# NuPrism_MCPMT_-_QUAD_ADC_-_Rev2.net
KiCad netlist of a schematic drawn in Altium Designer
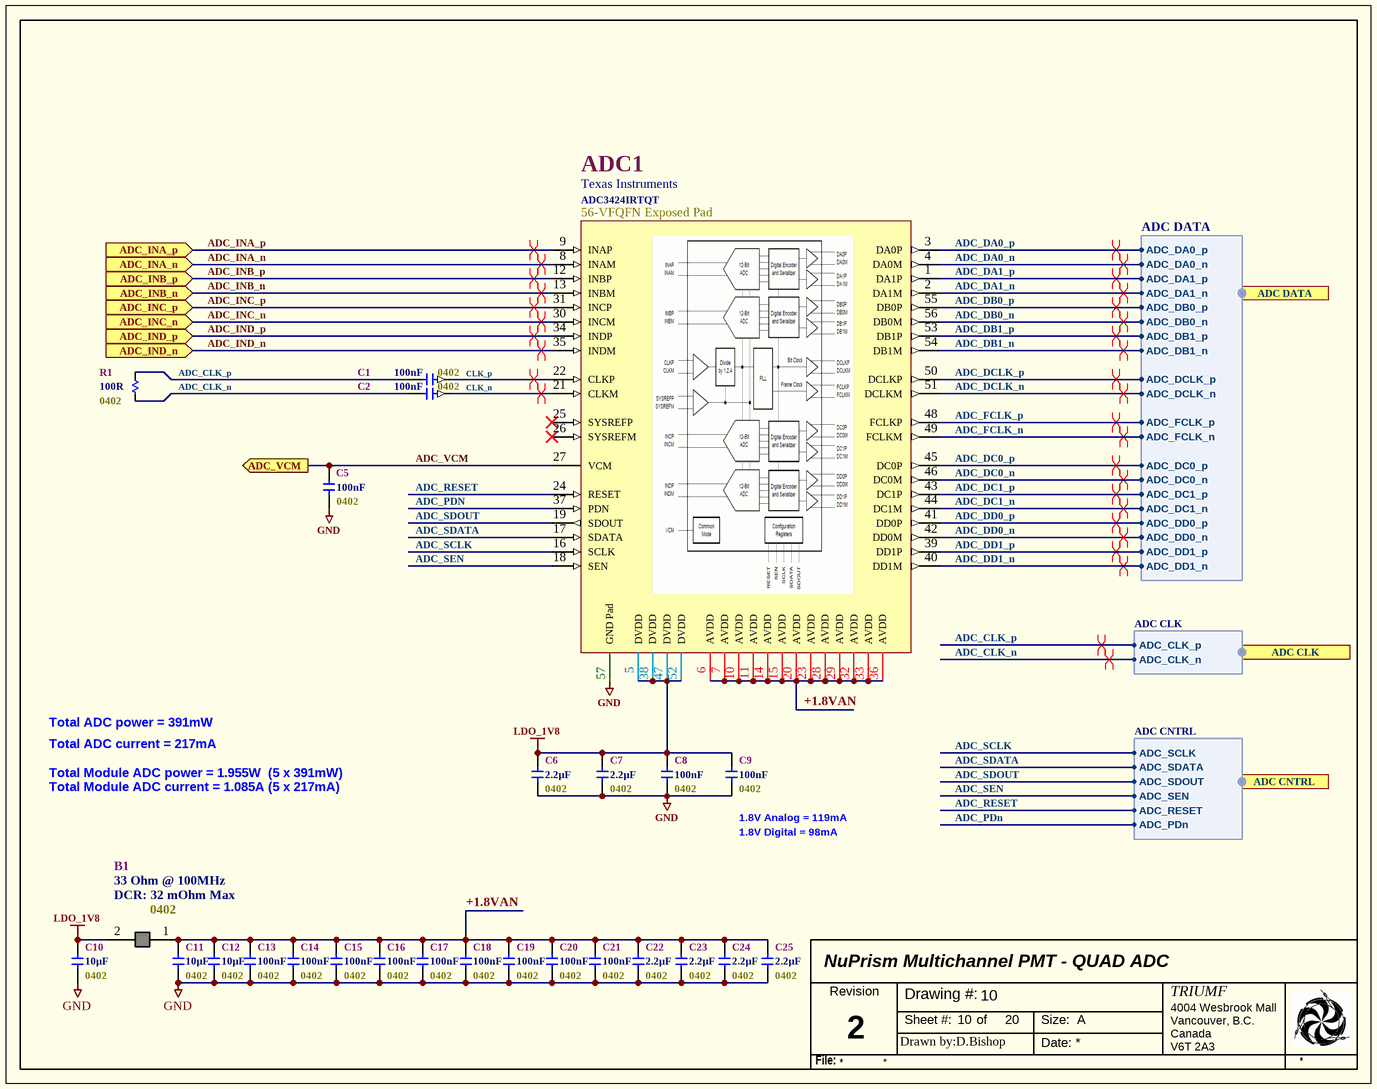
[diagram p0: NuPrism_MCPMT - QUAD ADC - Rev2.SchDoc]

(export (version "E")
  (design (tool "Eeschema 10.0.6"))
  (components
    (comp (ref "ADC1")
      (value "ADC3424IRTQT")
      (footprint "VQFN56")
      (description "12 Bit Analog to Digital Converter 4 Input 4 Pipelined 56-QFN (8x8)")
      (fields
        (field (name "MANUFACTURER") "Texas Instruments")
        (field (name "PACKAGE") "56-VFQFN Exposed Pad")
        (field (name "PARTNO") "ADC3424IRTQT")
      )
      (libsource (lib "TI_ADC") (part "ADC3424"))
    )
    (comp (ref "B1")
      (value "BLM15PX600SN1D")
      (footprint "0402")
      (description "60 Ohms @ 100MHz Ferrite Bead 0402 2.5A")
      (fields
        (field (name "MANUFACTURER") "Murata")
        (field (name "DCR") "32 mOhm Max")
        (field (name "IMPEDANCE @ FREQUENCY") "33 Ohm @ 100MHz")
        (field (name "PACKAGE") "0402")
      )
      (libsource (lib "Clock Distribution Module") (part "Ferrite Bead"))
    )
    (comp (ref "C1")
      (value "C0402C104K4RACTU")
      (footprint "0402")
      (description "SMD/SMT 0402 16V 0.1uF X7R 10%")
      (fields
        (field (name "MANUFACTURER") "Kemet")
        (field (name "CAPACITANCE") "100nF")
        (field (name "PACKAGE") "0402")
        (field (name "VOLTAGE") "16V")
      )
      (libsource (lib "NuPrism_MCPMT") (part "CAP-SMALL"))
    )
    (comp (ref "C2")
      (value "C0402C104K4RACTU")
      (footprint "0402")
      (description "SMD/SMT 0402 16V 0.1uF X7R 10%")
      (fields
        (field (name "MANUFACTURER") "Kemet")
        (field (name "CAPACITANCE") "100nF")
        (field (name "PACKAGE") "0402")
        (field (name "VOLTAGE") "16V")
      )
      (libsource (lib "NuPrism_MCPMT") (part "CAP-SMALL"))
    )
    (comp (ref "C5")
      (value "C0402C104K4RACTU")
      (footprint "0402")
      (description "SMD/SMT 0402 16V 0.1uF X7R 10%")
      (fields
        (field (name "MANUFACTURER") "Kemet")
        (field (name "CAPACITANCE") "100nF")
        (field (name "PACKAGE") "0402")
        (field (name "VOLTAGE") "16V")
      )
      (libsource (lib "NuPrism_MCPMT") (part "CAP-SMALL"))
    )
    (comp (ref "C6")
      (value "TMK105CBJ225KV-F")
      (footprint "0402")
      (description "SMD/SMT 0402 25V 2.2uF 10% X5R")
      (fields
        (field (name "MANUFACTURER") "Taiyo Yuden")
        (field (name "CAPACITANCE") "2.2µF")
        (field (name "PACKAGE") "0402")
        (field (name "VOLTAGE") "25V")
      )
      (libsource (lib "altium-import") (part "root_0_CAP-SMALL_"))
    )
    (comp (ref "C7")
      (value "TMK105CBJ225KV-F")
      (footprint "0402")
      (description "SMD/SMT 0402 25V 2.2uF 10% X5R")
      (fields
        (field (name "MANUFACTURER") "Taiyo Yuden")
        (field (name "CAPACITANCE") "2.2µF")
        (field (name "PACKAGE") "0402")
        (field (name "VOLTAGE") "25V")
      )
      (libsource (lib "altium-import") (part "root_0_CAP-SMALL_"))
    )
    (comp (ref "C8")
      (value "C0402C104K4RACTU")
      (footprint "0402")
      (description "SMD/SMT 0402 16V 0.1uF X7R 10%")
      (fields
        (field (name "MANUFACTURER") "Kemet")
        (field (name "CAPACITANCE") "100nF")
        (field (name "PACKAGE") "0402")
        (field (name "VOLTAGE") "16V")
      )
      (libsource (lib "NuPrism_MCPMT") (part "CAP-SMALL"))
    )
    (comp (ref "C9")
      (value "C0402C104K4RACTU")
      (footprint "0402")
      (description "SMD/SMT 0402 16V 0.1uF X7R 10%")
      (fields
        (field (name "MANUFACTURER") "Kemet")
        (field (name "CAPACITANCE") "100nF")
        (field (name "PACKAGE") "0402")
        (field (name "VOLTAGE") "16V")
      )
      (libsource (lib "NuPrism_MCPMT") (part "CAP-SMALL"))
    )
    (comp (ref "C10")
      (value "CL05A106MQ5NRNC")
      (footprint "0402")
      (description "10 µF ±20% 6.3V Ceramic Capacitor X5R 0402 (1005 Metric)")
      (fields
        (field (name "CAPACITANCE") "10µF")
        (field (name "PACKAGE") "0402")
        (field (name "MANUFACTURER") "Samsung Electro-Mechanics")
        (field (name "VOLTAGE") "6.3V")
      )
      (libsource (lib "altium-import") (part "root_2_CAP-SMALL_"))
    )
    (comp (ref "C11")
      (value "CL05A106MQ5NRNC")
      (footprint "0402")
      (description "10 µF ±20% 6.3V Ceramic Capacitor X5R 0402 (1005 Metric)")
      (fields
        (field (name "CAPACITANCE") "10µF")
        (field (name "PACKAGE") "0402")
        (field (name "MANUFACTURER") "Samsung Electro-Mechanics")
        (field (name "VOLTAGE") "6.3V")
      )
      (libsource (lib "altium-import") (part "root_2_CAP-SMALL_"))
    )
    (comp (ref "C12")
      (value "CL05A106MQ5NRNC")
      (footprint "0402")
      (description "10 µF ±20% 6.3V Ceramic Capacitor X5R 0402 (1005 Metric)")
      (fields
        (field (name "CAPACITANCE") "10µF")
        (field (name "PACKAGE") "0402")
        (field (name "MANUFACTURER") "Samsung Electro-Mechanics")
        (field (name "VOLTAGE") "6.3V")
      )
      (libsource (lib "altium-import") (part "root_2_CAP-SMALL_"))
    )
    (comp (ref "C13")
      (value "C0402C104K4RACTU")
      (footprint "0402")
      (description "SMD/SMT 0402 16V 0.1uF X7R 10%")
      (fields
        (field (name "MANUFACTURER") "Kemet")
        (field (name "CAPACITANCE") "100nF")
        (field (name "PACKAGE") "0402")
        (field (name "VOLTAGE") "16V")
      )
      (libsource (lib "NuPrism_MCPMT") (part "CAP-SMALL"))
    )
    (comp (ref "C14")
      (value "C0402C104K4RACTU")
      (footprint "0402")
      (description "SMD/SMT 0402 16V 0.1uF X7R 10%")
      (fields
        (field (name "MANUFACTURER") "Kemet")
        (field (name "CAPACITANCE") "100nF")
        (field (name "PACKAGE") "0402")
        (field (name "VOLTAGE") "16V")
      )
      (libsource (lib "NuPrism_MCPMT") (part "CAP-SMALL"))
    )
    (comp (ref "C15")
      (value "C0402C104K4RACTU")
      (footprint "0402")
      (description "SMD/SMT 0402 16V 0.1uF X7R 10%")
      (fields
        (field (name "MANUFACTURER") "Kemet")
        (field (name "CAPACITANCE") "100nF")
        (field (name "PACKAGE") "0402")
        (field (name "VOLTAGE") "16V")
      )
      (libsource (lib "NuPrism_MCPMT") (part "CAP-SMALL"))
    )
    (comp (ref "C16")
      (value "C0402C104K4RACTU")
      (footprint "0402")
      (description "SMD/SMT 0402 16V 0.1uF X7R 10%")
      (fields
        (field (name "MANUFACTURER") "Kemet")
        (field (name "CAPACITANCE") "100nF")
        (field (name "PACKAGE") "0402")
        (field (name "VOLTAGE") "16V")
      )
      (libsource (lib "NuPrism_MCPMT") (part "CAP-SMALL"))
    )
    (comp (ref "C17")
      (value "C0402C104K4RACTU")
      (footprint "0402")
      (description "SMD/SMT 0402 16V 0.1uF X7R 10%")
      (fields
        (field (name "MANUFACTURER") "Kemet")
        (field (name "CAPACITANCE") "100nF")
        (field (name "PACKAGE") "0402")
        (field (name "VOLTAGE") "16V")
      )
      (libsource (lib "NuPrism_MCPMT") (part "CAP-SMALL"))
    )
    (comp (ref "C18")
      (value "C0402C104K4RACTU")
      (footprint "0402")
      (description "SMD/SMT 0402 16V 0.1uF X7R 10%")
      (fields
        (field (name "MANUFACTURER") "Kemet")
        (field (name "CAPACITANCE") "100nF")
        (field (name "PACKAGE") "0402")
        (field (name "VOLTAGE") "16V")
      )
      (libsource (lib "NuPrism_MCPMT") (part "CAP-SMALL"))
    )
    (comp (ref "C19")
      (value "C0402C104K4RACTU")
      (footprint "0402")
      (description "SMD/SMT 0402 16V 0.1uF X7R 10%")
      (fields
        (field (name "MANUFACTURER") "Kemet")
        (field (name "CAPACITANCE") "100nF")
        (field (name "PACKAGE") "0402")
        (field (name "VOLTAGE") "16V")
      )
      (libsource (lib "NuPrism_MCPMT") (part "CAP-SMALL"))
    )
    (comp (ref "C20")
      (value "C0402C104K4RACTU")
      (footprint "0402")
      (description "SMD/SMT 0402 16V 0.1uF X7R 10%")
      (fields
        (field (name "MANUFACTURER") "Kemet")
        (field (name "CAPACITANCE") "100nF")
        (field (name "PACKAGE") "0402")
        (field (name "VOLTAGE") "16V")
      )
      (libsource (lib "NuPrism_MCPMT") (part "CAP-SMALL"))
    )
    (comp (ref "C21")
      (value "C0402C104K4RACTU")
      (footprint "0402")
      (description "SMD/SMT 0402 16V 0.1uF X7R 10%")
      (fields
        (field (name "MANUFACTURER") "Kemet")
        (field (name "CAPACITANCE") "100nF")
        (field (name "PACKAGE") "0402")
        (field (name "VOLTAGE") "16V")
      )
      (libsource (lib "NuPrism_MCPMT") (part "CAP-SMALL"))
    )
    (comp (ref "C22")
      (value "TMK105CBJ225KV-F")
      (footprint "0402")
      (description "SMD/SMT 0402 25V 2.2uF 10% X5R")
      (fields
        (field (name "MANUFACTURER") "Taiyo Yuden")
        (field (name "CAPACITANCE") "2.2µF")
        (field (name "PACKAGE") "0402")
        (field (name "VOLTAGE") "25V")
      )
      (libsource (lib "altium-import") (part "root_0_CAP-SMALL_"))
    )
    (comp (ref "C23")
      (value "TMK105CBJ225KV-F")
      (footprint "0402")
      (description "SMD/SMT 0402 25V 2.2uF 10% X5R")
      (fields
        (field (name "MANUFACTURER") "Taiyo Yuden")
        (field (name "CAPACITANCE") "2.2µF")
        (field (name "PACKAGE") "0402")
        (field (name "VOLTAGE") "25V")
      )
      (libsource (lib "altium-import") (part "root_0_CAP-SMALL_"))
    )
    (comp (ref "C24")
      (value "TMK105CBJ225KV-F")
      (footprint "0402")
      (description "SMD/SMT 0402 25V 2.2uF 10% X5R")
      (fields
        (field (name "MANUFACTURER") "Taiyo Yuden")
        (field (name "CAPACITANCE") "2.2µF")
        (field (name "PACKAGE") "0402")
        (field (name "VOLTAGE") "25V")
      )
      (libsource (lib "altium-import") (part "root_0_CAP-SMALL_"))
    )
    (comp (ref "C25")
      (value "TMK105CBJ225KV-F")
      (footprint "0402")
      (description "SMD/SMT 0402 25V 2.2uF 10% X5R")
      (fields
        (field (name "MANUFACTURER") "Taiyo Yuden")
        (field (name "CAPACITANCE") "2.2µF")
        (field (name "PACKAGE") "0402")
        (field (name "VOLTAGE") "25V")
      )
      (libsource (lib "altium-import") (part "root_0_CAP-SMALL_"))
    )
    (comp (ref "R1")
      (value "RMCF0402FT100R")
      (footprint "0402")
      (description "100 Ohms ±1% 0.063W, 1/16W Chip Resistor 0402 (1005 Metric)")
      (fields
        (field (name "MANUFACTURER") "Stackpole Electronics Inc")
        (field (name "RESISTANCE") "100R")
        (field (name "PACKAGE") "0402")
      )
      (libsource (lib "NuPrism - mPMT") (part "RES-TINY"))
    )
  )
  (nets
    (net (code "5") (name "/+1.8VAN") (class "Default")
      (node (ref "ADC1") (pin "10") (pinfunction "AVDD_10") (pintype "power_in"))
      (node (ref "ADC1") (pin "11") (pinfunction "AVDD_11") (pintype "power_in"))
      (node (ref "ADC1") (pin "14") (pinfunction "AVDD_14") (pintype "power_in"))
      (node (ref "ADC1") (pin "15") (pinfunction "AVDD_15") (pintype "power_in"))
      (node (ref "ADC1") (pin "20") (pinfunction "AVDD_20") (pintype "power_in"))
      (node (ref "ADC1") (pin "23") (pinfunction "AVDD_23") (pintype "power_in"))
      (node (ref "ADC1") (pin "28") (pinfunction "AVDD_28") (pintype "power_in"))
      (node (ref "ADC1") (pin "29") (pinfunction "AVDD_29") (pintype "power_in"))
      (node (ref "ADC1") (pin "32") (pinfunction "AVDD_32") (pintype "power_in"))
      (node (ref "ADC1") (pin "33") (pinfunction "AVDD_33") (pintype "power_in"))
      (node (ref "ADC1") (pin "36") (pinfunction "AVDD_36") (pintype "power_in"))
      (node (ref "ADC1") (pin "6") (pinfunction "AVDD_6") (pintype "power_in"))
      (node (ref "ADC1") (pin "7") (pinfunction "AVDD_7") (pintype "power_in"))
      (node (ref "B1") (pin "1") (pinfunction "1_1") (pintype "passive"))
      (node (ref "C11") (pin "2") (pintype "passive"))
      (node (ref "C12") (pin "2") (pintype "passive"))
      (node (ref "C13") (pin "1") (pintype "output"))
      (node (ref "C14") (pin "1") (pintype "output"))
      (node (ref "C15") (pin "1") (pintype "output"))
      (node (ref "C16") (pin "1") (pintype "output"))
      (node (ref "C17") (pin "1") (pintype "output"))
      (node (ref "C18") (pin "1") (pintype "output"))
      (node (ref "C19") (pin "1") (pintype "output"))
      (node (ref "C20") (pin "1") (pintype "output"))
      (node (ref "C21") (pin "1") (pintype "output"))
      (node (ref "C22") (pin "1") (pintype "passive"))
      (node (ref "C23") (pin "1") (pintype "passive"))
      (node (ref "C24") (pin "1") (pintype "passive"))
      (node (ref "C25") (pin "1") (pintype "passive"))
    )
    (net (code "6") (name "/ADC_CLK_n") (class "Default")
      (node (ref "C2") (pin "2") (pintype "passive"))
      (node (ref "R1") (pin "2") (pintype "passive"))
    )
    (net (code "7") (name "/ADC_CLK_p") (class "Default")
      (node (ref "C1") (pin "2") (pintype "passive"))
      (node (ref "R1") (pin "1") (pintype "passive"))
    )
    (net (code "8") (name "/ADC_DA0_n") (class "Default")
      (node (ref "ADC1") (pin "4") (pinfunction "DA0M_4") (pintype "output"))
    )
    (net (code "9") (name "/ADC_DA0_p") (class "Default")
      (node (ref "ADC1") (pin "3") (pinfunction "DA0P_3") (pintype "output"))
    )
    (net (code "10") (name "/ADC_DA1_n") (class "Default")
      (node (ref "ADC1") (pin "2") (pinfunction "DA1M_2") (pintype "output"))
    )
    (net (code "11") (name "/ADC_DA1_p") (class "Default")
      (node (ref "ADC1") (pin "1") (pinfunction "DA1P_1") (pintype "output"))
    )
    (net (code "12") (name "/ADC_DB0_n") (class "Default")
      (node (ref "ADC1") (pin "56") (pinfunction "DB0M_56") (pintype "output"))
    )
    (net (code "13") (name "/ADC_DB0_p") (class "Default")
      (node (ref "ADC1") (pin "55") (pinfunction "DB0P_55") (pintype "output"))
    )
    (net (code "14") (name "/ADC_DB1_n") (class "Default")
      (node (ref "ADC1") (pin "54") (pinfunction "DB1M_54") (pintype "output"))
    )
    (net (code "15") (name "/ADC_DB1_p") (class "Default")
      (node (ref "ADC1") (pin "53") (pinfunction "DB1P_53") (pintype "output"))
    )
    (net (code "16") (name "/ADC_DC0_n") (class "Default")
      (node (ref "ADC1") (pin "46") (pinfunction "DC0M_46") (pintype "output"))
    )
    (net (code "17") (name "/ADC_DC0_p") (class "Default")
      (node (ref "ADC1") (pin "45") (pinfunction "DC0P_45") (pintype "output"))
    )
    (net (code "18") (name "/ADC_DC1_n") (class "Default")
      (node (ref "ADC1") (pin "44") (pinfunction "DC1M_44") (pintype "output"))
    )
    (net (code "19") (name "/ADC_DC1_p") (class "Default")
      (node (ref "ADC1") (pin "43") (pinfunction "DC1P_43") (pintype "output"))
    )
    (net (code "20") (name "/ADC_DCLK_n") (class "Default")
      (node (ref "ADC1") (pin "51") (pinfunction "DCLKM_51") (pintype "output"))
    )
    (net (code "21") (name "/ADC_DCLK_p") (class "Default")
      (node (ref "ADC1") (pin "50") (pinfunction "DCLKP_50") (pintype "output"))
    )
    (net (code "22") (name "/ADC_DD0_n") (class "Default")
      (node (ref "ADC1") (pin "42") (pinfunction "DD0M_42") (pintype "output"))
    )
    (net (code "23") (name "/ADC_DD0_p") (class "Default")
      (node (ref "ADC1") (pin "41") (pinfunction "DD0P_41") (pintype "output"))
    )
    (net (code "24") (name "/ADC_DD1_n") (class "Default")
      (node (ref "ADC1") (pin "40") (pinfunction "DD1M_40") (pintype "output"))
    )
    (net (code "25") (name "/ADC_DD1_p") (class "Default")
      (node (ref "ADC1") (pin "39") (pinfunction "DD1P_39") (pintype "output"))
    )
    (net (code "26") (name "/ADC_FCLK_n") (class "Default")
      (node (ref "ADC1") (pin "49") (pinfunction "FCLKM_49") (pintype "output"))
    )
    (net (code "27") (name "/ADC_FCLK_p") (class "Default")
      (node (ref "ADC1") (pin "48") (pinfunction "FCLKP_48") (pintype "output"))
    )
    (net (code "28") (name "/ADC_INA_n") (class "Default")
      (node (ref "ADC1") (pin "8") (pinfunction "INAM_8") (pintype "input"))
    )
    (net (code "29") (name "/ADC_INA_p") (class "Default")
      (node (ref "ADC1") (pin "9") (pinfunction "INAP_9") (pintype "input"))
    )
    (net (code "30") (name "/ADC_INB_n") (class "Default")
      (node (ref "ADC1") (pin "13") (pinfunction "INBM_13") (pintype "input"))
    )
    (net (code "31") (name "/ADC_INB_p") (class "Default")
      (node (ref "ADC1") (pin "12") (pinfunction "INBP_12") (pintype "input"))
    )
    (net (code "32") (name "/ADC_INC_n") (class "Default")
      (node (ref "ADC1") (pin "30") (pinfunction "INCM_30") (pintype "input"))
    )
    (net (code "33") (name "/ADC_INC_p") (class "Default")
      (node (ref "ADC1") (pin "31") (pinfunction "INCP_31") (pintype "input"))
    )
    (net (code "34") (name "/ADC_IND_n") (class "Default")
      (node (ref "ADC1") (pin "35") (pinfunction "INDM_35") (pintype "input"))
    )
    (net (code "35") (name "/ADC_IND_p") (class "Default")
      (node (ref "ADC1") (pin "34") (pinfunction "INDP_34") (pintype "input"))
    )
    (net (code "36") (name "/ADC_PDN") (class "Default")
      (node (ref "ADC1") (pin "37") (pinfunction "PDN_37") (pintype "input"))
    )
    (net (code "38") (name "/ADC_RESET") (class "Default")
      (node (ref "ADC1") (pin "24") (pinfunction "RESET_24") (pintype "input"))
    )
    (net (code "39") (name "/ADC_SCLK") (class "Default")
      (node (ref "ADC1") (pin "16") (pinfunction "SCLK_16") (pintype "input"))
    )
    (net (code "40") (name "/ADC_SDATA") (class "Default")
      (node (ref "ADC1") (pin "17") (pinfunction "SDATA_17") (pintype "input"))
    )
    (net (code "41") (name "/ADC_SDOUT") (class "Default")
      (node (ref "ADC1") (pin "19") (pinfunction "SDOUT_19") (pintype "output"))
    )
    (net (code "42") (name "/ADC_SEN") (class "Default")
      (node (ref "ADC1") (pin "18") (pinfunction "SEN_18") (pintype "input"))
    )
    (net (code "43") (name "/ADC_VCM") (class "Default")
      (node (ref "ADC1") (pin "27") (pinfunction "VCM_27") (pintype "passive"))
      (node (ref "C5") (pin "1") (pintype "output"))
    )
    (net (code "44") (name "/CLK_n") (class "Default")
      (node (ref "ADC1") (pin "21") (pinfunction "CLKM_21") (pintype "input"))
      (node (ref "C2") (pin "1") (pintype "output"))
    )
    (net (code "45") (name "/CLK_p") (class "Default")
      (node (ref "ADC1") (pin "22") (pinfunction "CLKP_22") (pintype "input"))
      (node (ref "C1") (pin "1") (pintype "output"))
    )
    (net (code "49") (name "GND") (class "Default")
      (node (ref "ADC1") (pin "57") (pinfunction "GND_Pad_57") (pintype "power_in"))
      (node (ref "C10") (pin "1") (pintype "passive"))
      (node (ref "C11") (pin "1") (pintype "passive"))
      (node (ref "C12") (pin "1") (pintype "passive"))
      (node (ref "C13") (pin "2") (pintype "passive"))
      (node (ref "C14") (pin "2") (pintype "passive"))
      (node (ref "C15") (pin "2") (pintype "passive"))
      (node (ref "C16") (pin "2") (pintype "passive"))
      (node (ref "C17") (pin "2") (pintype "passive"))
      (node (ref "C18") (pin "2") (pintype "passive"))
      (node (ref "C19") (pin "2") (pintype "passive"))
      (node (ref "C20") (pin "2") (pintype "passive"))
      (node (ref "C21") (pin "2") (pintype "passive"))
      (node (ref "C22") (pin "2") (pintype "passive"))
      (node (ref "C23") (pin "2") (pintype "passive"))
      (node (ref "C24") (pin "2") (pintype "passive"))
      (node (ref "C25") (pin "2") (pintype "passive"))
      (node (ref "C5") (pin "2") (pintype "passive"))
      (node (ref "C6") (pin "2") (pintype "passive"))
      (node (ref "C7") (pin "2") (pintype "passive"))
      (node (ref "C8") (pin "2") (pintype "passive"))
      (node (ref "C9") (pin "2") (pintype "passive"))
    )
    (net (code "50") (name "LDO_1V8") (class "Default")
      (node (ref "ADC1") (pin "38") (pinfunction "DVDD_38") (pintype "power_in"))
      (node (ref "ADC1") (pin "47") (pinfunction "DVDD_47") (pintype "power_in"))
      (node (ref "ADC1") (pin "5") (pinfunction "DVDD_5") (pintype "power_in"))
      (node (ref "ADC1") (pin "52") (pinfunction "DVDD_52") (pintype "power_in"))
      (node (ref "B1") (pin "2") (pinfunction "2_2") (pintype "passive"))
      (node (ref "C10") (pin "2") (pintype "passive"))
      (node (ref "C6") (pin "1") (pintype "passive"))
      (node (ref "C7") (pin "1") (pintype "passive"))
      (node (ref "C8") (pin "1") (pintype "output"))
      (node (ref "C9") (pin "1") (pintype "output"))
    )
    (net (code "51") (name "unconnected-(ADC1-SYSREFM-Pad26)") (class "Default")
      (node (ref "ADC1") (pin "26") (pinfunction "SYSREFM_26") (pintype "input+no_connect"))
    )
    (net (code "52") (name "unconnected-(ADC1-SYSREFP-Pad25)") (class "Default")
      (node (ref "ADC1") (pin "25") (pinfunction "SYSREFP_25") (pintype "input+no_connect"))
    )
  )
)
